# soldeerstation_twee.net
KiCad netlist of a schematic drawn in Altium Designer
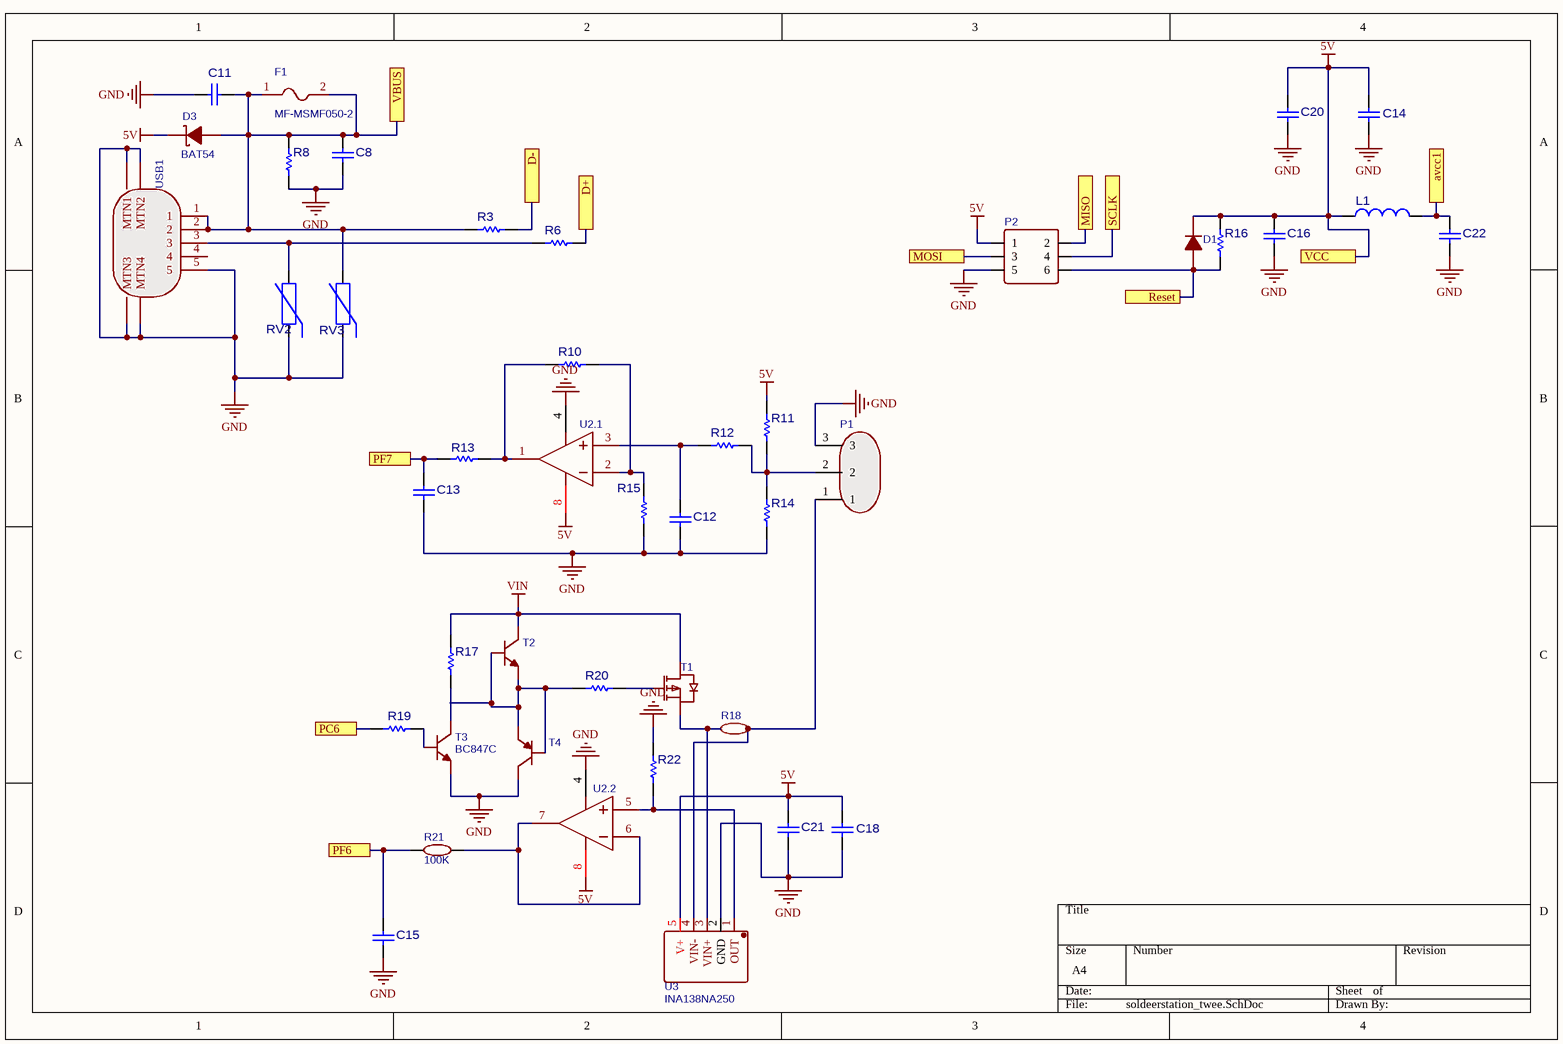
[diagram p0: soldeerstation_twee.SchDoc]

(export (version "E")
  (design (tool "Eeschema 10.0.6"))
  (components
    (comp (ref "C8")
      (value "C0402C104K8PACTU")
      (footprint "CAPC1005X60X30ML05T10")
      (fields (field (name "MANUFACTURER") "Kemet"))
      (libsource (lib "Altium Content Vault") (part "CAP"))
    )
    (comp (ref "C11")
      (value "GRM219R61A226MEA0D")
      (footprint "CAPC2013X95X45ML15T25")
      (fields (field (name "MANUFACTURER") "Murata"))
      (libsource (lib "Altium Content Vault") (part "CAP"))
    )
    (comp (ref "C12")
      (value "GRM188R71H103KA01D")
      (footprint "CAPC1608X90X35ML10T15")
      (description "Chip Capacitor, 10 nF, +/- 10%, 50 V, -55 to 125 degC, 0603 (1608 Metric), RoHS, Tape and Reel")
      (fields (field (name "VOLTAGE") "50V") (field (name "TOLERANCE") "10%"))
      (libsource (lib "Altium Content Vault") (part "CAP-NP-2"))
    )
    (comp (ref "C13")
      (value "GRM188R71H103KA01D")
      (footprint "CAPC1608X90X35ML10T15")
      (description "Chip Capacitor, 10 nF, +/- 10%, 50 V, -55 to 125 degC, 0603 (1608 Metric), RoHS, Tape and Reel")
      (fields (field (name "VOLTAGE") "50V") (field (name "TOLERANCE") "10%"))
      (libsource (lib "Altium Content Vault") (part "CAP-NP-2"))
    )
    (comp (ref "C14")
      (value "C0402C104K8PACTU")
      (footprint "CAPC1005X60X30ML05T10")
      (fields (field (name "MANUFACTURER") "Kemet"))
      (libsource (lib "Altium Content Vault") (part "CAP"))
    )
    (comp (ref "C15")
      (value "12061C105KAT2A")
      (footprint "CAPC3216X180X50LL20T25")
      (description "Chip Capacitor, 1 uF, +/- 10%, 100 V, -55 to 125 degC, 1206 (3216 Metric), RoHS, Tape and Reel")
      (fields (field (name "MANUFACTURER") "AVX"))
      (libsource (lib "Altium Content Vault") (part "CAP-NP-2"))
    )
    (comp (ref "C16")
      (value "C0402C104K8PACTU")
      (footprint "CAPC1005X60X30ML05T10")
      (fields (field (name "MANUFACTURER") "Kemet"))
      (libsource (lib "Altium Content Vault") (part "CAP"))
    )
    (comp (ref "C18")
      (value "C1206C106K8RACTU")
      (footprint "CAPC3216X180X50LL20T25")
      (description "Chip Capacitor, 10 uF, +/- 10%, 10 V, -55 to 125 degC, 1206 (3216 Metric), RoHS, Tape and Reel")
      (fields (field (name "TOLERANCE") "10%") (field (name "MANUFACTURER") "Kemet"))
      (libsource (lib "Altium Content Vault") (part "CAP-NP-2"))
    )
    (comp (ref "C20")
      (value "C1206C106K8RACTU")
      (footprint "CAPC3216X180X50LL20T25")
      (description "Chip Capacitor, 10 uF, +/- 10%, 10 V, -55 to 125 degC, 1206 (3216 Metric), RoHS, Tape and Reel")
      (fields (field (name "TOLERANCE") "10%") (field (name "MANUFACTURER") "Kemet"))
      (libsource (lib "Altium Content Vault") (part "CAP-NP-2"))
    )
    (comp (ref "C21")
      (value "C0402C104K8PACTU")
      (footprint "CAPC1005X60X30ML05T10")
      (fields (field (name "MANUFACTURER") "Kemet"))
      (libsource (lib "Altium Content Vault") (part "CAP"))
    )
    (comp (ref "C22")
      (value "12061C105KAT2A")
      (footprint "CAPC3216X180X50LL20T25")
      (description "Chip Capacitor, 1 uF, +/- 10%, 100 V, -55 to 125 degC, 1206 (3216 Metric), RoHS, Tape and Reel")
      (fields (field (name "MANUFACTURER") "AVX"))
      (libsource (lib "Altium Content Vault") (part "CAP-NP-2"))
    )
    (comp (ref "D1")
      (value "CD1206-S01575")
      (footprint "D-1206")
      (fields (field (name "BOM_SUPPLIER PART") "C75465") (field (name "CONTRIBUTOR") "LCSC"))
      (libsource (lib "PCB_Project") (part "CD1206-S01575"))
    )
    (comp (ref "D3")
      (value "BAT54")
      (footprint "SOT-23(SOT-23-3)")
      (fields (field (name "BOM_SUPPLIER PART") "C181198") (field (name "CONTRIBUTOR") "LCSC"))
      (libsource (lib "PCB_Project") (part "BAT54"))
    )
    (comp (ref "F1")
      (value "MF-MSMF050-2")
      (footprint "1812")
      (fields (field (name "BOM_SUPPLIER PART") "C17313"))
      (libsource (lib "soldeerstation") (part "MF-MSMF050-2"))
    )
    (comp (ref "L1")
      (value "74279206")
      (footprint "SMD-0805")
      (description "SMD EMI Suppression Ferrite Bead WE-CBF, Z = 30 Ohm")
      (libsource (lib "Altium Content Vault") (part "PAS-IND-INDUCTOR-2"))
    )
    (comp (ref "P1")
      (value "WJ25C-B-7.62-3P-13-00A")
      (footprint "WJ25C-B-7.62-3P")
      (fields (field (name "BOM_SUPPLIER PART") "C61583"))
      (libsource (lib "PCB_Project") (part "WJ25C-B-7.62-3P-13-00A"))
    )
    (comp (ref "P2")
      (value "Header-Male-2.54_2x3")
      (footprint "HDR-3X2/2.54")
      (fields (field (name "BOM_SUPPLIER PART") "C65114"))
      (libsource (lib "PCB_Project") (part "Header-Male-2.54_2x3"))
    )
    (comp (ref "R3")
      (value "ERJ-2RKF22R0X")
      (footprint "RESC1005X40X25ML05T05")
      (description "Chip Resistor, 22 Ohm, +/- 1%, 0.1 W, -55 to 155 degC, 0402 (1005 Metric), RoHS, Tape and Reel")
      (fields (field (name "TOLERANCE") "1%"))
      (libsource (lib "Altium Content Vault") (part "RES-2"))
    )
    (comp (ref "R6")
      (value "ERJ-2RKF22R0X")
      (footprint "RESC1005X40X25ML05T05")
      (description "Chip Resistor, 22 Ohm, +/- 1%, 0.1 W, -55 to 155 degC, 0402 (1005 Metric), RoHS, Tape and Reel")
      (fields (field (name "TOLERANCE") "1%"))
      (libsource (lib "Altium Content Vault") (part "RES-2"))
    )
    (comp (ref "R8")
      (value "RC0603FR-0710KL")
      (footprint "RESC1608X55X25ML10T15")
      (description "Chip Resistor, 10 KOhm, +/- 1%, 01 W, -55 to 155 degC, 0603 (1608 Metric), RoHS, Tape and Reel")
      (fields (field (name "MANUFACTURER") "Yageo") (field (name "TOLERANCE") "1%"))
      (libsource (lib "Altium Content Vault") (part "RES-2"))
    )
    (comp (ref "R10")
      (value "ERJ2RKF1802X")
      (footprint "RESC1005X40X25NL05T05")
      (fields (field (name "MANUFACTURER") "Panasonic"))
      (libsource (lib "Altium Content Vault") (part "RES"))
    )
    (comp (ref "R11")
      (value "ERJ-2RKF1004X")
      (footprint "RESC1005X40X25LL05T05")
      (description "Chip Resistor, 1 MOhm, +/- 1%, 100 mW, -55 to 155 degC, 0402 (1005 Metric), RoHS, Tape and Reel")
      (fields (field (name "TOLERANCE") "1%") (field (name "MANUFACTURER") "Basic Passives"))
      (libsource (lib "Altium Content Vault") (part "RES-2"))
    )
    (comp (ref "R12")
      (value "ERJ2RKF5601X")
      (footprint "RESC1005X40X25LL05T05")
      (fields (field (name "MANUFACTURER") "Panasonic"))
      (libsource (lib "Altium Content Vault") (part "RES"))
    )
    (comp (ref "R13")
      (value "ERJ2RKF5601X")
      (footprint "RESC1005X40X25LL05T05")
      (fields (field (name "MANUFACTURER") "Panasonic"))
      (libsource (lib "Altium Content Vault") (part "RES"))
    )
    (comp (ref "R14")
      (value "CRCW060310M0FKEA")
      (footprint "RESC1609X50X30ML10T20")
      (fields (field (name "MANUFACTURER") "Vishay Dale"))
      (libsource (lib "Altium Content Vault") (part "RES"))
    )
    (comp (ref "R15")
      (value "91R 1% 0603(1608)")
      (footprint "RESC0603(1608)_L")
      (description "91R 0.1W 1% 0603 (1608 Metric)  SMD")
      (fields (field (name "POWER") "0.1 W") (field (name "TOLERANCE") "1 %"))
      (libsource (lib "Altium Content Vault") (part "RES"))
    )
    (comp (ref "R16")
      (value "RC0603FR-0710KL")
      (footprint "RESC1608X55X25ML10T15")
      (description "Chip Resistor, 10 KOhm, +/- 1%, 01 W, -55 to 155 degC, 0603 (1608 Metric), RoHS, Tape and Reel")
      (fields (field (name "MANUFACTURER") "Yageo") (field (name "TOLERANCE") "1%"))
      (libsource (lib "Altium Content Vault") (part "RES-2"))
    )
    (comp (ref "R17")
      (value "ERJ-3EKF4701V")
      (footprint "RESC1608X55X30NL15T15")
      (fields (field (name "TOLERANCE") "5%"))
      (libsource (lib "Altium Content Vault") (part "RES-2"))
    )
    (comp (ref "R18")
      (value "0.02")
      (footprint "LR12DL1020LJ")
      (fields
        (field (name "BOM_MANUFACTURER PART") "LR12DL1020LJ")
        (field (name "BOM_SUPPLIER PART") "C159865")
        (field (name "CONTRIBUTOR") "LCSC")
      )
      (libsource (lib "soldeerstation") (part "0.02"))
    )
    (comp (ref "R19")
      (value "RC0603FR-0710KL")
      (footprint "RESC1608X55X25ML10T15")
      (description "Chip Resistor, 10 KOhm, +/- 1%, 01 W, -55 to 155 degC, 0603 (1608 Metric), RoHS, Tape and Reel")
      (fields (field (name "MANUFACTURER") "Yageo") (field (name "TOLERANCE") "1%"))
      (libsource (lib "Altium Content Vault") (part "RES-2"))
    )
    (comp (ref "R20")
      (value "91R 1% 0603(1608)")
      (footprint "RESC0603(1608)_L")
      (description "91R 0.1W 1% 0603 (1608 Metric)  SMD")
      (fields (field (name "POWER") "0.1 W") (field (name "TOLERANCE") "1 %"))
      (libsource (lib "Altium Content Vault") (part "RES"))
    )
    (comp (ref "R21")
      (value "100K")
      (footprint "0805")
      (fields
        (field (name "BOM_MANUFACTURER PART") "TC0525F1003T5E")
        (field (name "BOM_SUPPLIER PART") "C57246")
      )
      (libsource (lib "soldeerstation") (part "100K"))
    )
    (comp (ref "R22")
      (value "ERJ2RKF5603X")
      (footprint "RESC1005X40X25NL05T05")
      (fields (field (name "MANUFACTURER") "Panasonic"))
      (libsource (lib "Altium Content Vault") (part "RES"))
    )
    (comp (ref "RV2")
      (value "CG0603MLC-05E")
      (footprint "BOUR-CG0603-2_V")
      (description "ESD Protector, 5 V Supply, -40 to 85 degC, 1.6 x 0.8 x 0.55 mm SMD, RoHS, Tape and Reel")
      (fields (field (name "MANUFACTURER") "Bourns"))
      (libsource (lib "Altium Content Vault") (part "BOUR-VSR-2"))
    )
    (comp (ref "RV3")
      (value "CG0603MLC-05E")
      (footprint "BOUR-CG0603-2_V")
      (description "ESD Protector, 5 V Supply, -40 to 85 degC, 1.6 x 0.8 x 0.55 mm SMD, RoHS, Tape and Reel")
      (fields (field (name "MANUFACTURER") "Bourns"))
      (libsource (lib "Altium Content Vault") (part "BOUR-VSR-2"))
    )
    (comp (ref "T1")
      (value "IRF9540NPBF")
      (footprint "TO-220(TO-220-3)")
      (fields (field (name "BOM_SUPPLIER PART") "C2575"))
      (libsource (lib "PCB_Project") (part "IRF9540NPBF"))
    )
    (comp (ref "T2")
      (value "BC847C")
      (footprint "SOT-23(SOT-23-3)")
      (fields (field (name "BOM_SUPPLIER PART") "C181141") (field (name "CONTRIBUTOR") "LCSC"))
      (libsource (lib "PCB_Project") (part "BC847C"))
    )
    (comp (ref "T3")
      (value "BC847C")
      (footprint "SOT-23(SOT-23-3)")
      (fields (field (name "BOM_SUPPLIER PART") "C181141") (field (name "CONTRIBUTOR") "LCSC"))
      (libsource (lib "PCB_Project") (part "BC847C"))
    )
    (comp (ref "T4")
      (value "BC857C")
      (footprint "SOT-23(SOT-23-3)")
      (fields (field (name "BOM_SUPPLIER PART") "C181147") (field (name "CONTRIBUTOR") "LCSC"))
      (libsource (lib "PCB_Project") (part "BC857C"))
    )
    (comp (ref "U2.1")
      (value "MCP6002T-E/SN")
      (footprint "SOIC-8_150MIL")
      (fields (field (name "BOM_SUPPLIER PART") "C125816") (field (name "SUBPART_NO") "2"))
      (libsource (lib "PCB_Project") (part "MCP6002T-E/SN_1"))
    )
    (comp (ref "U2.2")
      (value "MCP6002T-E/SN")
      (footprint "SOIC-8_150MIL")
      (fields (field (name "BOM_SUPPLIER PART") "C125816") (field (name "SUBPART_NO") "1"))
      (libsource (lib "PCB_Project") (part "MCP6002T-E/SN"))
    )
    (comp (ref "U3")
      (value "INA138NA250")
      (footprint "SOT-23-5")
      (fields (field (name "BOM_SUPPLIER PART") "C133804") (field (name "CONTRIBUTOR") "LCSC"))
      (libsource (lib "PCB_Project") (part "INA138NA250"))
    )
    (comp (ref "USB1")
      (value "micro USB_B Female")
      (footprint "MICRO-USB-1")
      (fields
        (field (name "BOM_MANUFACTURER PART") "micro USBFemale")
        (field (name "BOM_SUPPLIER PART") "C10418")
      )
      (libsource (lib "PCB_Project") (part "micro USB_B Female"))
    )
  )
  (nets
    (net (code "1") (name "/D+") (class "Default")
      (node (ref "R6") (pin "2") (pinfunction "2_2") (pintype "passive"))
    )
    (net (code "2") (name "/D-") (class "Default")
      (node (ref "R3") (pin "2") (pinfunction "2_2") (pintype "passive"))
    )
    (net (code "3") (name "/MISO") (class "Default")
      (node (ref "P2") (pin "2") (pinfunction "2_2") (pintype "passive"))
    )
    (net (code "4") (name "/MOSI") (class "Default")
      (node (ref "P2") (pin "3") (pinfunction "3_3") (pintype "passive"))
    )
    (net (code "5") (name "/PC6") (class "Default")
      (node (ref "R19") (pin "1") (pinfunction "1_1") (pintype "passive"))
    )
    (net (code "6") (name "/PF6") (class "Default")
      (node (ref "C15") (pin "2") (pinfunction "2_2") (pintype "passive"))
      (node (ref "R21") (pin "1") (pinfunction "1_1") (pintype "passive"))
    )
    (net (code "7") (name "/PF7") (class "Default")
      (node (ref "C13") (pin "2") (pinfunction "2_2") (pintype "passive"))
      (node (ref "R13") (pin "1") (pinfunction "1_1") (pintype "passive"))
    )
    (net (code "8") (name "/Reset") (class "Default")
      (node (ref "D1") (pin "1") (pinfunction "A_1") (pintype "passive"))
      (node (ref "P2") (pin "6") (pinfunction "6_6") (pintype "passive"))
      (node (ref "R16") (pin "2") (pinfunction "2_2") (pintype "passive"))
    )
    (net (code "9") (name "/SCLK") (class "Default")
      (node (ref "P2") (pin "4") (pinfunction "4_4") (pintype "passive"))
    )
    (net (code "10") (name "/VBUS") (class "Default")
      (node (ref "C11") (pin "2") (pinfunction "2_2") (pintype "passive"))
      (node (ref "C8") (pin "2") (pinfunction "2_2") (pintype "passive"))
      (node (ref "D3") (pin "1") (pinfunction "A_1") (pintype "passive"))
      (node (ref "F1") (pin "1") (pinfunction "1_1") (pintype "passive"))
      (node (ref "F1") (pin "2") (pinfunction "2_2") (pintype "passive"))
      (node (ref "R3") (pin "1") (pinfunction "1_1") (pintype "passive"))
      (node (ref "R8") (pin "2") (pinfunction "2_2") (pintype "passive"))
      (node (ref "RV3") (pin "2") (pinfunction "2_2") (pintype "passive"))
      (node (ref "USB1") (pin "1") (pinfunction "1_1") (pintype "passive"))
      (node (ref "USB1") (pin "2") (pinfunction "2_2") (pintype "passive"))
    )
    (net (code "11") (name "/avcc1") (class "Default")
      (node (ref "C22") (pin "1") (pinfunction "1_1") (pintype "passive"))
      (node (ref "L1") (pin "2") (pinfunction "2_2") (pintype "passive"))
    )
    (net (code "12") (name "5V") (class "Default")
      (node (ref "C14") (pin "2") (pinfunction "2_2") (pintype "passive"))
      (node (ref "C16") (pin "1") (pinfunction "1_1") (pintype "passive"))
      (node (ref "C18") (pin "2") (pinfunction "2_2") (pintype "passive"))
      (node (ref "C20") (pin "2") (pinfunction "2_2") (pintype "passive"))
      (node (ref "C21") (pin "2") (pinfunction "2_2") (pintype "passive"))
      (node (ref "D1") (pin "2") (pinfunction "K_2") (pintype "passive"))
      (node (ref "D3") (pin "3") (pinfunction "K_3") (pintype "passive"))
      (node (ref "L1") (pin "1") (pinfunction "1_1") (pintype "passive"))
      (node (ref "P2") (pin "1") (pinfunction "1_1") (pintype "passive"))
      (node (ref "R11") (pin "2") (pinfunction "2_2") (pintype "passive"))
      (node (ref "R16") (pin "1") (pinfunction "1_1") (pintype "passive"))
      (node (ref "U2.1") (pin "8") (pinfunction "VDD_8") (pintype "passive"))
      (node (ref "U2.2") (pin "8") (pinfunction "VDD_8") (pintype "passive"))
      (node (ref "U3") (pin "5") (pinfunction "V+_5") (pintype "passive"))
    )
    (net (code "13") (name "GND") (class "Default")
      (node (ref "C11") (pin "1") (pinfunction "1_1") (pintype "passive"))
      (node (ref "C12") (pin "1") (pinfunction "1_1") (pintype "passive"))
      (node (ref "C13") (pin "1") (pinfunction "1_1") (pintype "passive"))
      (node (ref "C14") (pin "1") (pinfunction "1_1") (pintype "passive"))
      (node (ref "C15") (pin "1") (pinfunction "1_1") (pintype "passive"))
      (node (ref "C16") (pin "2") (pinfunction "2_2") (pintype "passive"))
      (node (ref "C18") (pin "1") (pinfunction "1_1") (pintype "passive"))
      (node (ref "C20") (pin "1") (pinfunction "1_1") (pintype "passive"))
      (node (ref "C21") (pin "1") (pinfunction "1_1") (pintype "passive"))
      (node (ref "C22") (pin "2") (pinfunction "2_2") (pintype "passive"))
      (node (ref "C8") (pin "1") (pinfunction "1_1") (pintype "passive"))
      (node (ref "P1") (pin "3") (pinfunction "3_3") (pintype "passive"))
      (node (ref "P2") (pin "5") (pinfunction "5_5") (pintype "passive"))
      (node (ref "R14") (pin "1") (pinfunction "1_1") (pintype "passive"))
      (node (ref "R15") (pin "2") (pinfunction "2_2") (pintype "passive"))
      (node (ref "R22") (pin "1") (pinfunction "1_1") (pintype "passive"))
      (node (ref "R8") (pin "1") (pinfunction "1_1") (pintype "passive"))
      (node (ref "RV2") (pin "1") (pinfunction "1_1") (pintype "passive"))
      (node (ref "RV3") (pin "1") (pinfunction "1_1") (pintype "passive"))
      (node (ref "T3") (pin "2") (pinfunction "E_2") (pintype "passive"))
      (node (ref "T4") (pin "3") (pinfunction "C_3") (pintype "passive"))
      (node (ref "U2.1") (pin "4") (pinfunction "VSS_4") (pintype "passive"))
      (node (ref "U2.2") (pin "4") (pinfunction "VSS_4") (pintype "passive"))
      (node (ref "U3") (pin "2") (pinfunction "GND_2") (pintype "passive"))
      (node (ref "USB1") (pin "0") (pinfunction "MTN4_0") (pintype "passive"))
      (node (ref "USB1") (pin "5") (pinfunction "5_5") (pintype "passive"))
    )
    (net (code "14") (name "Net-(P1-Pad2)") (class "Default")
      (node (ref "P1") (pin "2") (pinfunction "2_2") (pintype "passive"))
      (node (ref "R11") (pin "1") (pinfunction "1_1") (pintype "passive"))
      (node (ref "R12") (pin "2") (pinfunction "2_2") (pintype "passive"))
      (node (ref "R14") (pin "2") (pinfunction "2_2") (pintype "passive"))
    )
    (net (code "15") (name "Net-(R6-Pad1)") (class "Default")
      (node (ref "R6") (pin "1") (pinfunction "1_1") (pintype "passive"))
      (node (ref "RV2") (pin "2") (pinfunction "2_2") (pintype "passive"))
      (node (ref "USB1") (pin "3") (pinfunction "3_3") (pintype "passive"))
    )
    (net (code "16") (name "Net-(T1-G)") (class "Default")
      (node (ref "R20") (pin "2") (pinfunction "2_2") (pintype "passive"))
      (node (ref "T1") (pin "1") (pinfunction "G_1") (pintype "passive"))
    )
    (net (code "17") (name "Net-(T1-S)") (class "Default")
      (node (ref "R18") (pin "1") (pinfunction "1_1") (pintype "passive"))
      (node (ref "T1") (pin "3") (pinfunction "S_3") (pintype "passive"))
      (node (ref "U3") (pin "3") (pinfunction "VIN+_3") (pintype "passive"))
    )
    (net (code "18") (name "Net-(T2-B)") (class "Default")
      (node (ref "R20") (pin "1") (pinfunction "1_1") (pintype "passive"))
      (node (ref "T2") (pin "1") (pinfunction "B_1") (pintype "passive"))
      (node (ref "T2") (pin "2") (pinfunction "E_2") (pintype "passive"))
      (node (ref "T4") (pin "1") (pinfunction "B_1") (pintype "passive"))
      (node (ref "T4") (pin "2") (pinfunction "E_2") (pintype "passive"))
    )
    (net (code "19") (name "Net-(T3-B)") (class "Default")
      (node (ref "R19") (pin "2") (pinfunction "2_2") (pintype "passive"))
      (node (ref "T3") (pin "1") (pinfunction "B_1") (pintype "passive"))
    )
    (net (code "20") (name "Net-(T3-C)") (class "Default")
      (node (ref "R17") (pin "1") (pinfunction "1_1") (pintype "passive"))
      (node (ref "T3") (pin "3") (pinfunction "C_3") (pintype "passive"))
    )
    (net (code "21") (name "Net-(U2.1-VINA+)") (class "Default")
      (node (ref "C12") (pin "2") (pinfunction "2_2") (pintype "passive"))
      (node (ref "R12") (pin "1") (pinfunction "1_1") (pintype "passive"))
      (node (ref "U2.1") (pin "3") (pinfunction "VINA+_3") (pintype "passive"))
    )
    (net (code "22") (name "Net-(U2.1-VINA-)") (class "Default")
      (node (ref "R10") (pin "2") (pinfunction "2_2") (pintype "passive"))
      (node (ref "R15") (pin "1") (pinfunction "1_1") (pintype "passive"))
      (node (ref "U2.1") (pin "2") (pinfunction "VINA-_2") (pintype "passive"))
    )
    (net (code "23") (name "Net-(U2.1-VOUTA)") (class "Default")
      (node (ref "R10") (pin "1") (pinfunction "1_1") (pintype "passive"))
      (node (ref "R13") (pin "2") (pinfunction "2_2") (pintype "passive"))
      (node (ref "U2.1") (pin "1") (pinfunction "VOUTA_1") (pintype "passive"))
    )
    (net (code "24") (name "Net-(U2.2-VINB+)") (class "Default")
      (node (ref "R22") (pin "2") (pinfunction "2_2") (pintype "passive"))
      (node (ref "U2.2") (pin "5") (pinfunction "VINB+_5") (pintype "passive"))
      (node (ref "U3") (pin "1") (pinfunction "OUT_1") (pintype "passive"))
    )
    (net (code "25") (name "Net-(U2.2-VINB-)") (class "Default")
      (node (ref "R21") (pin "2") (pinfunction "2_2") (pintype "passive"))
      (node (ref "U2.2") (pin "6") (pinfunction "VINB-_6") (pintype "passive"))
      (node (ref "U2.2") (pin "7") (pinfunction "VOUTB_7") (pintype "passive"))
    )
    (net (code "26") (name "Net-(U3-VIN-)") (class "Default")
      (node (ref "P1") (pin "1") (pinfunction "1_1") (pintype "passive"))
      (node (ref "R18") (pin "2") (pinfunction "2_2") (pintype "passive"))
      (node (ref "U3") (pin "4") (pinfunction "VIN-_4") (pintype "passive"))
    )
    (net (code "27") (name "VIN") (class "Default")
      (node (ref "R17") (pin "2") (pinfunction "2_2") (pintype "passive"))
      (node (ref "T1") (pin "2") (pinfunction "D_2") (pintype "passive"))
      (node (ref "T2") (pin "3") (pinfunction "C_3") (pintype "passive"))
    )
    (net (code "28") (name "unconnected-(USB1-Pad4)") (class "Default")
      (node (ref "USB1") (pin "4") (pinfunction "4_4") (pintype "passive"))
    )
  )
)
